# FOTA_MicroController_Power_Switch.net
KiCad netlist of a schematic drawn in Altium Designer
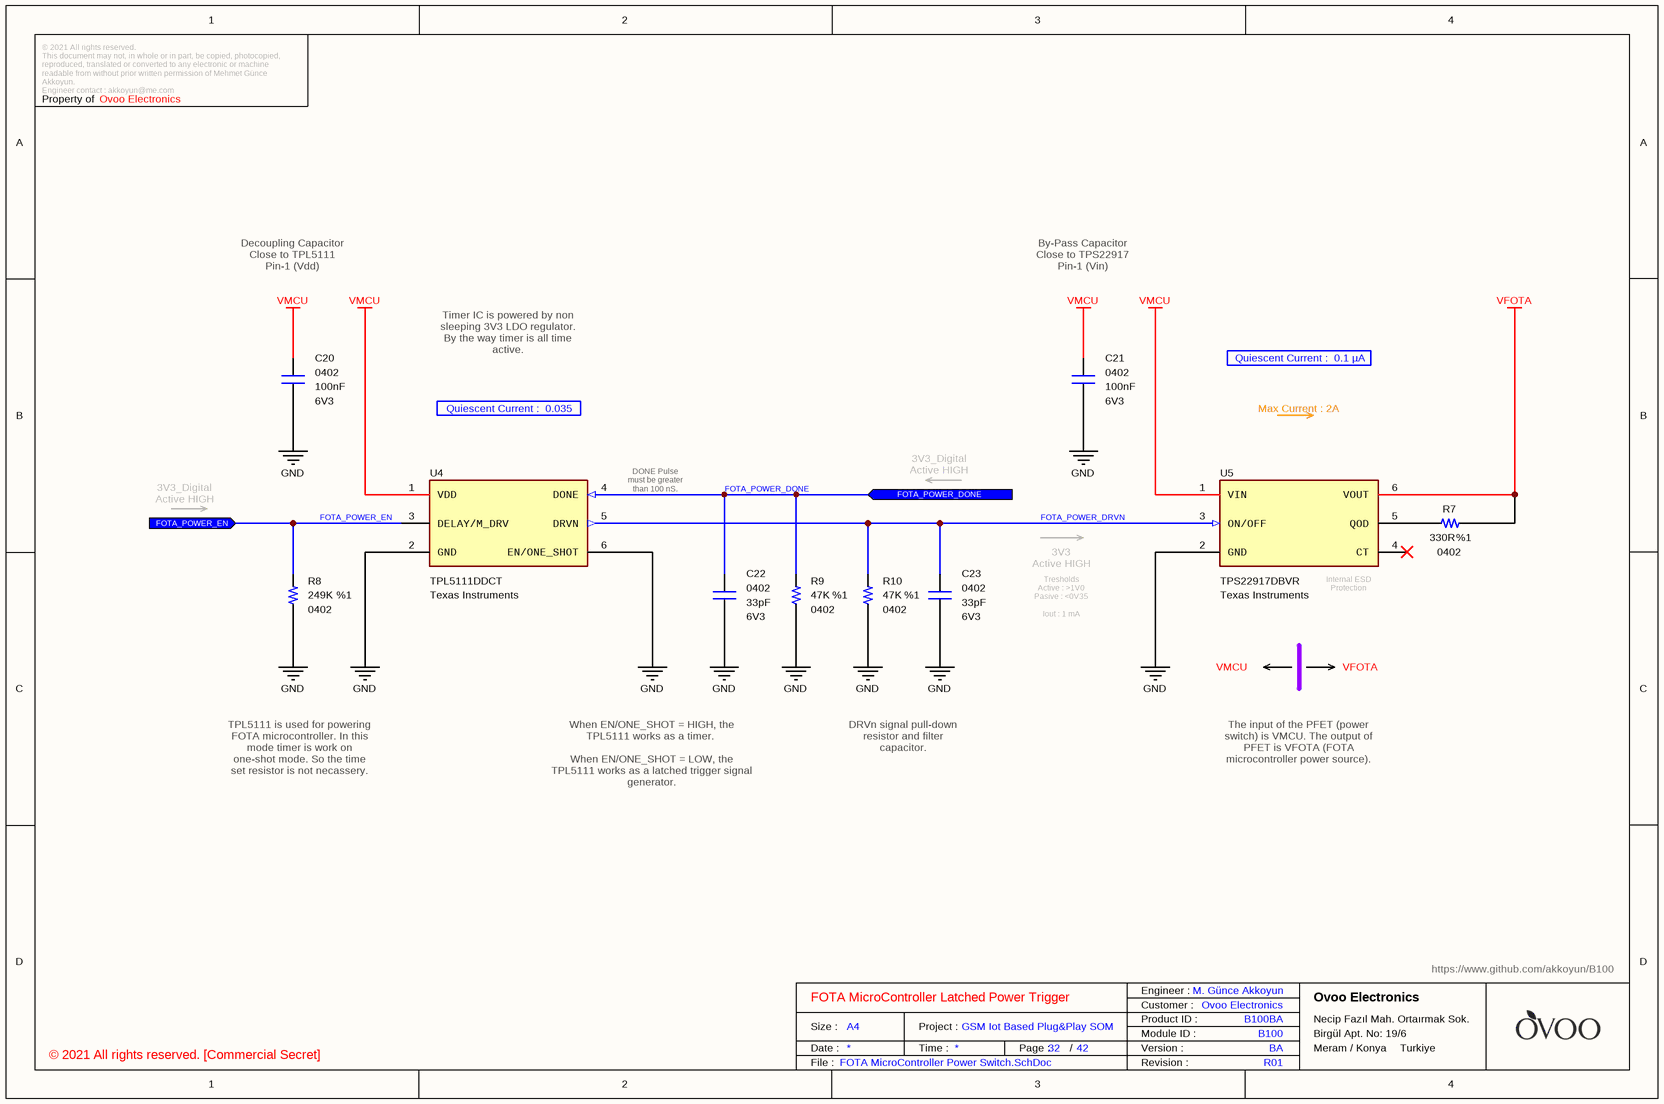
[diagram p0: FOTA MicroController Power Switch.SchDoc]

(export (version "E")
  (design (tool "Eeschema 10.0.6"))
  (components
    (comp (ref "C20")
      (value "100nF")
      (footprint "CAPACITOR_0402")
      (description "Capacitor - 100nF [0402-6V3] (Ceramic)")
      (fields
        (field (name "TOLERANCE") "%10")
        (field (name "CASE") "0402")
        (field (name "VOLTAGE") "6V3")
        (field (name "MANUFACTURER PART NUMBER") "04026D104KAT4A")
      )
      (libsource (lib "Ovoo_Library") (part "Capacitor - 100nF [0402-6V3]"))
    )
    (comp (ref "C21")
      (value "100nF")
      (footprint "CAPACITOR_0402")
      (description "Capacitor - 100nF [0402-6V3] (Ceramic)")
      (fields
        (field (name "CASE") "0402")
        (field (name "TOLERANCE") "%10")
        (field (name "VOLTAGE") "6V3")
        (field (name "MANUFACTURER PART NUMBER") "04026D104KAT4A")
      )
      (libsource (lib "Ovoo_Library") (part "Capacitor - 100nF [0402-6V3]"))
    )
    (comp (ref "C22")
      (value "33pF")
      (footprint "CAPACITOR_0402")
      (description "Capacitor - 33pF [0402] (Ceramic)")
      (fields
        (field (name "TOLERANCE") "10%")
        (field (name "CASE") "0402")
        (field (name "VOLTAGE") "6V3")
        (field (name "MANUFACTURER PART NUMBER") "C0402C330J9RACAUTO")
      )
      (libsource (lib "Ovoo_Library") (part "Capacitor - 33pF [0402-6V3]"))
    )
    (comp (ref "C23")
      (value "33pF")
      (footprint "CAPACITOR_0402")
      (description "Capacitor - 33pF [0402] (Ceramic)")
      (fields
        (field (name "TOLERANCE") "10%")
        (field (name "CASE") "0402")
        (field (name "VOLTAGE") "6V3")
        (field (name "MANUFACTURER PART NUMBER") "C0402C330J9RACAUTO")
      )
      (libsource (lib "Ovoo_Library") (part "Capacitor - 33pF [0402-6V3]"))
    )
    (comp (ref "R7")
      (value "330R")
      (footprint "RESISTOR_0402")
      (description "Thick Film Resistors - SMD 1/16 W 330 Ohm 1%")
      (fields
        (field (name "TOLERANCE") "%1")
        (field (name "CASE") "0402")
        (field (name "MANUFACTURER PART NUMBER") "CRCW0402330RFKED")
        (field (name "MOUSER PART NUMBER") "71-CRCW0402-330-E3")
      )
      (libsource (lib "Ovoo_Library") (part "Resistor - 330R"))
    )
    (comp (ref "R8")
      (value "249K")
      (footprint "RESISTOR_0402")
      (description "Thick Film Resistors - SMD 1/16 W 249 Kohms 1%")
      (fields
        (field (name "TOLERANCE") "%1")
        (field (name "CASE") "0402")
        (field (name "MANUFACTURER PART NUMBER") "CRCW0402249KFKED")
        (field (name "MOUSER PART NUMBER") "71-CRCW0402-249K-E3")
      )
      (libsource (lib "Ovoo_Library") (part "Resistor - 249K"))
    )
    (comp (ref "R9")
      (value "47K")
      (footprint "RESISTOR_0402")
      (description "Thick Film Resistors - SMD 1/16 W 47 Kohms 1%")
      (fields
        (field (name "TOLERANCE") "%1")
        (field (name "CASE") "0402")
        (field (name "MANUFACTURER PART NUMBER") "CRCW040247K0FKED")
        (field (name "Comment") "47K - 0402 - %1 - 1/16W")
      )
      (libsource (lib "Ovoo_Library") (part "Resistor - 47K"))
    )
    (comp (ref "R10")
      (value "47K")
      (footprint "RESISTOR_0402")
      (description "Thick Film Resistors - SMD 1/16 W 47 Kohms 1%")
      (fields
        (field (name "TOLERANCE") "%1")
        (field (name "CASE") "0402")
        (field (name "MANUFACTURER PART NUMBER") "CRCW040247K0FKED")
        (field (name "Comment") "47K - 0402 - %1 - 1/16W")
      )
      (libsource (lib "Ovoo_Library") (part "Resistor - 47K"))
    )
    (comp (ref "U4")
      (value "Nanopower Timer IC")
      (footprint "SOT-23-6")
      (fields
        (field (name "MOUSER PART NUMBER") "595-TPL5111DDCT")
        (field (name "MANUFACTURER PART NUMBER") "TPL5111DDCT")
        (field (name "MANUFACTURER NAME") "Texas Instruments")
      )
      (libsource (lib "Ovoo_Library") (part "IC - TPL5111"))
    )
    (comp (ref "U5")
      (value "Power Switch")
      (footprint "SOT-23-6")
      (description "Power Switch MosFet")
      (fields
        (field (name "MOUSER PART NUMBER") "595-TPS22917DBVR")
        (field (name "MANUFACTURER PART NUMBER") "TPS22917DBVR")
        (field (name "MANUFACTURER NAME") "Texas Instruments")
      )
      (libsource (lib "Ovoo_Library") (part "IC - TPS22917DBVR"))
    )
  )
  (nets
    (net (code "1") (name "/FOTA_POWER_DONE") (class "Default")
      (node (ref "C22") (pin "2") (pinfunction "2_2") (pintype "passive"))
      (node (ref "R9") (pin "2") (pinfunction "2_2") (pintype "passive"))
      (node (ref "U4") (pin "4") (pinfunction "DONE_4") (pintype "input"))
    )
    (net (code "2") (name "/FOTA_POWER_DRVN") (class "Default")
      (node (ref "C23") (pin "2") (pinfunction "2_2") (pintype "passive"))
      (node (ref "R10") (pin "2") (pinfunction "2_2") (pintype "passive"))
      (node (ref "U4") (pin "5") (pinfunction "DRVN_5") (pintype "output"))
      (node (ref "U5") (pin "3") (pinfunction "ON/OFF_3") (pintype "input"))
    )
    (net (code "3") (name "/FOTA_POWER_EN") (class "Default")
      (node (ref "R8") (pin "2") (pinfunction "2_2") (pintype "passive"))
      (node (ref "U4") (pin "3") (pinfunction "DELAY/M_DRV_3") (pintype "passive"))
    )
    (net (code "4") (name "GND") (class "Default")
      (node (ref "C20") (pin "1") (pinfunction "1_1") (pintype "passive"))
      (node (ref "C21") (pin "2") (pinfunction "2_2") (pintype "passive"))
      (node (ref "C22") (pin "1") (pinfunction "1_1") (pintype "passive"))
      (node (ref "C23") (pin "1") (pinfunction "1_1") (pintype "passive"))
      (node (ref "R10") (pin "1") (pinfunction "1_1") (pintype "passive"))
      (node (ref "R8") (pin "1") (pinfunction "1_1") (pintype "passive"))
      (node (ref "R9") (pin "1") (pinfunction "1_1") (pintype "passive"))
      (node (ref "U4") (pin "2") (pinfunction "GND_2") (pintype "power_in"))
      (node (ref "U4") (pin "6") (pinfunction "EN/ONE_SHOT_6") (pintype "passive"))
      (node (ref "U5") (pin "2") (pinfunction "GND_2") (pintype "power_in"))
    )
    (net (code "5") (name "Net-(U5-QOD)") (class "Default")
      (node (ref "R7") (pin "2") (pinfunction "2_2") (pintype "passive"))
      (node (ref "U5") (pin "5") (pinfunction "QOD_5") (pintype "power_in"))
    )
    (net (code "6") (name "VFOTA") (class "Default")
      (node (ref "R7") (pin "1") (pinfunction "1_1") (pintype "passive"))
      (node (ref "U5") (pin "6") (pinfunction "VOUT_6") (pintype "power_in"))
    )
    (net (code "7") (name "VMCU") (class "Default")
      (node (ref "C20") (pin "2") (pinfunction "2_2") (pintype "passive"))
      (node (ref "C21") (pin "1") (pinfunction "1_1") (pintype "passive"))
      (node (ref "U4") (pin "1") (pinfunction "VDD_1") (pintype "power_in"))
      (node (ref "U5") (pin "1") (pinfunction "VIN_1") (pintype "power_in"))
    )
    (net (code "8") (name "unconnected-(U5-CT-Pad4)") (class "Default")
      (node (ref "U5") (pin "4") (pinfunction "CT_4") (pintype "power_in+no_connect"))
    )
  )
)
